# lm324.net
KiCad netlist of a schematic drawn in EAGLE
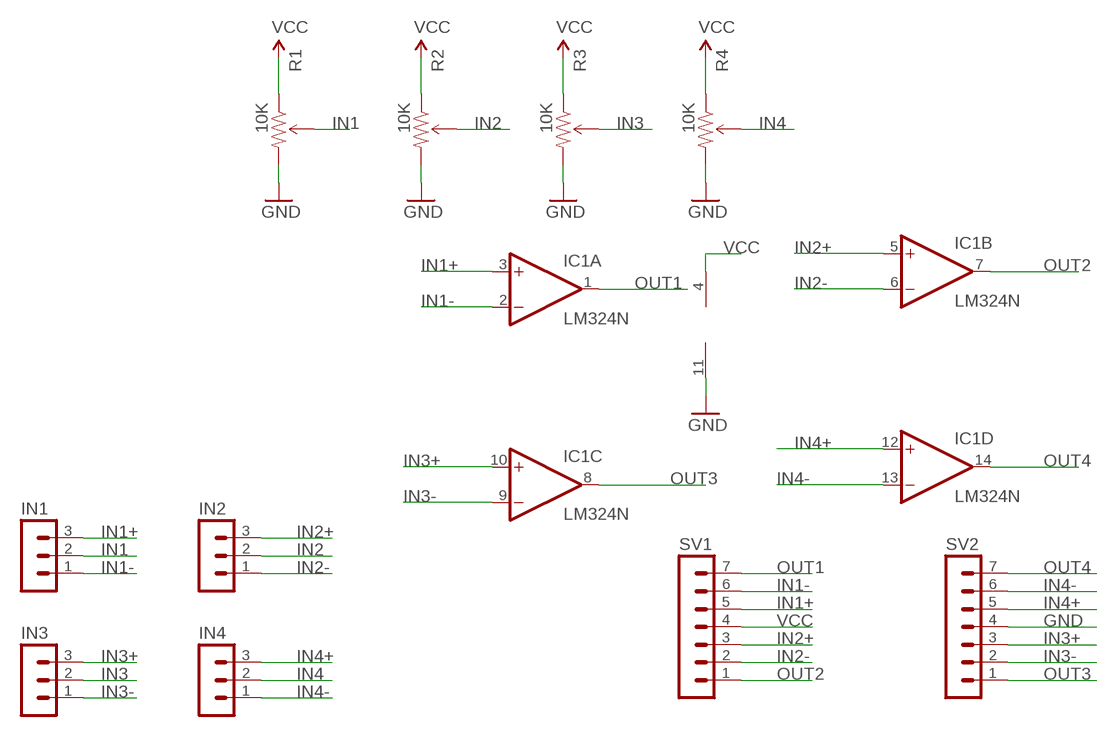
[diagram p0: schematic, sheet 1]

(export (version "E")
  (design (tool "Eeschema 10.0.6"))
  (components
    (comp (ref "IC1")
      (value "LM324N")
      (footprint "eagle-import:DIL14")
      (libsource (lib "eagle-import") (part "LM324N"))
    )
    (comp (ref "IN1")
      (value "MA03-1")
      (footprint "eagle-import:MA03-1")
      (libsource (lib "eagle-import") (part "MA03-1"))
    )
    (comp (ref "IN2")
      (value "MA03-1")
      (footprint "eagle-import:MA03-1")
      (libsource (lib "eagle-import") (part "MA03-1"))
    )
    (comp (ref "IN3")
      (value "MA03-1")
      (footprint "eagle-import:MA03-1")
      (libsource (lib "eagle-import") (part "MA03-1"))
    )
    (comp (ref "IN4")
      (value "MA03-1")
      (footprint "eagle-import:MA03-1")
      (libsource (lib "eagle-import") (part "MA03-1"))
    )
    (comp (ref "R1")
      (value "10K")
      (footprint "eagle-import:TRIM_POT_PTH")
      (libsource (lib "eagle-import") (part "TRIMPOTPTH"))
    )
    (comp (ref "R2")
      (value "10K")
      (footprint "eagle-import:TRIM_POT_PTH")
      (libsource (lib "eagle-import") (part "TRIMPOTPTH"))
    )
    (comp (ref "R3")
      (value "10K")
      (footprint "eagle-import:TRIM_POT_PTH")
      (libsource (lib "eagle-import") (part "TRIMPOTPTH"))
    )
    (comp (ref "R4")
      (value "10K")
      (footprint "eagle-import:TRIM_POT_PTH")
      (libsource (lib "eagle-import") (part "TRIMPOTPTH"))
    )
    (comp (ref "SV1")
      (value "MA07-1")
      (footprint "eagle-import:MA07-1")
      (libsource (lib "eagle-import") (part "MA07-1"))
    )
    (comp (ref "SV2")
      (value "MA07-1")
      (footprint "eagle-import:MA07-1")
      (libsource (lib "eagle-import") (part "MA07-1"))
    )
  )
  (nets
    (net (code "1") (name "/IN1") (class "Default")
      (node (ref "IN1") (pin "2") (pinfunction "2_2") (pintype "passive"))
      (node (ref "R1") (pin "2") (pinfunction "WIPER_2") (pintype "passive"))
    )
    (net (code "2") (name "/IN1+") (class "Default")
      (node (ref "IC1") (pin "3") (pinfunction "+IN_3") (pintype "input"))
      (node (ref "IN1") (pin "3") (pinfunction "3_3") (pintype "passive"))
      (node (ref "SV1") (pin "5") (pinfunction "5_5") (pintype "passive"))
    )
    (net (code "3") (name "/IN1-") (class "Default")
      (node (ref "IC1") (pin "2") (pinfunction "-IN_2") (pintype "input"))
      (node (ref "IN1") (pin "1") (pinfunction "1_1") (pintype "passive"))
      (node (ref "SV1") (pin "6") (pinfunction "6_6") (pintype "passive"))
    )
    (net (code "4") (name "/IN2") (class "Default")
      (node (ref "IN2") (pin "2") (pinfunction "2_2") (pintype "passive"))
      (node (ref "R2") (pin "2") (pinfunction "WIPER_2") (pintype "passive"))
    )
    (net (code "5") (name "/IN2+") (class "Default")
      (node (ref "IC1") (pin "5") (pinfunction "+IN_5") (pintype "input"))
      (node (ref "IN2") (pin "3") (pinfunction "3_3") (pintype "passive"))
      (node (ref "SV1") (pin "3") (pinfunction "3_3") (pintype "passive"))
    )
    (net (code "6") (name "/IN2-") (class "Default")
      (node (ref "IC1") (pin "6") (pinfunction "-IN_6") (pintype "input"))
      (node (ref "IN2") (pin "1") (pinfunction "1_1") (pintype "passive"))
      (node (ref "SV1") (pin "2") (pinfunction "2_2") (pintype "passive"))
    )
    (net (code "7") (name "/IN3") (class "Default")
      (node (ref "IN3") (pin "2") (pinfunction "2_2") (pintype "passive"))
      (node (ref "R3") (pin "2") (pinfunction "WIPER_2") (pintype "passive"))
    )
    (net (code "8") (name "/IN3+") (class "Default")
      (node (ref "IC1") (pin "10") (pinfunction "+IN_10") (pintype "input"))
      (node (ref "IN3") (pin "3") (pinfunction "3_3") (pintype "passive"))
      (node (ref "SV2") (pin "3") (pinfunction "3_3") (pintype "passive"))
    )
    (net (code "9") (name "/IN3-") (class "Default")
      (node (ref "IC1") (pin "9") (pinfunction "-IN_9") (pintype "input"))
      (node (ref "IN3") (pin "1") (pinfunction "1_1") (pintype "passive"))
      (node (ref "SV2") (pin "2") (pinfunction "2_2") (pintype "passive"))
    )
    (net (code "10") (name "/IN4") (class "Default")
      (node (ref "IN4") (pin "2") (pinfunction "2_2") (pintype "passive"))
      (node (ref "R4") (pin "2") (pinfunction "WIPER_2") (pintype "passive"))
    )
    (net (code "11") (name "/IN4+") (class "Default")
      (node (ref "IC1") (pin "12") (pinfunction "+IN_12") (pintype "input"))
      (node (ref "IN4") (pin "3") (pinfunction "3_3") (pintype "passive"))
      (node (ref "SV2") (pin "5") (pinfunction "5_5") (pintype "passive"))
    )
    (net (code "12") (name "/IN4-") (class "Default")
      (node (ref "IC1") (pin "13") (pinfunction "-IN_13") (pintype "input"))
      (node (ref "IN4") (pin "1") (pinfunction "1_1") (pintype "passive"))
      (node (ref "SV2") (pin "6") (pinfunction "6_6") (pintype "passive"))
    )
    (net (code "13") (name "/OUT1") (class "Default")
      (node (ref "IC1") (pin "1") (pinfunction "OUT_1") (pintype "output"))
      (node (ref "SV1") (pin "7") (pinfunction "7_7") (pintype "passive"))
    )
    (net (code "14") (name "/OUT2") (class "Default")
      (node (ref "IC1") (pin "7") (pinfunction "OUT_7") (pintype "output"))
      (node (ref "SV1") (pin "1") (pinfunction "1_1") (pintype "passive"))
    )
    (net (code "15") (name "/OUT3") (class "Default")
      (node (ref "IC1") (pin "8") (pinfunction "OUT_8") (pintype "output"))
      (node (ref "SV2") (pin "1") (pinfunction "1_1") (pintype "passive"))
    )
    (net (code "16") (name "/OUT4") (class "Default")
      (node (ref "IC1") (pin "14") (pinfunction "OUT_14") (pintype "output"))
      (node (ref "SV2") (pin "7") (pinfunction "7_7") (pintype "passive"))
    )
    (net (code "17") (name "GND") (class "Default")
      (node (ref "IC1") (pin "11") (pinfunction "V-_11") (pintype "power_in"))
      (node (ref "R1") (pin "3") (pinfunction "CW_3") (pintype "passive"))
      (node (ref "R2") (pin "3") (pinfunction "CW_3") (pintype "passive"))
      (node (ref "R3") (pin "3") (pinfunction "CW_3") (pintype "passive"))
      (node (ref "R4") (pin "3") (pinfunction "CW_3") (pintype "passive"))
      (node (ref "SV2") (pin "4") (pinfunction "4_4") (pintype "passive"))
    )
    (net (code "18") (name "VCC") (class "Default")
      (node (ref "IC1") (pin "4") (pinfunction "V+_4") (pintype "power_in"))
      (node (ref "R1") (pin "1") (pinfunction "CCW_1") (pintype "passive"))
      (node (ref "R2") (pin "1") (pinfunction "CCW_1") (pintype "passive"))
      (node (ref "R3") (pin "1") (pinfunction "CCW_1") (pintype "passive"))
      (node (ref "R4") (pin "1") (pinfunction "CCW_1") (pintype "passive"))
      (node (ref "SV1") (pin "4") (pinfunction "4_4") (pintype "passive"))
    )
  )
)
